# random.net
KiCad netlist of a schematic drawn in EAGLE
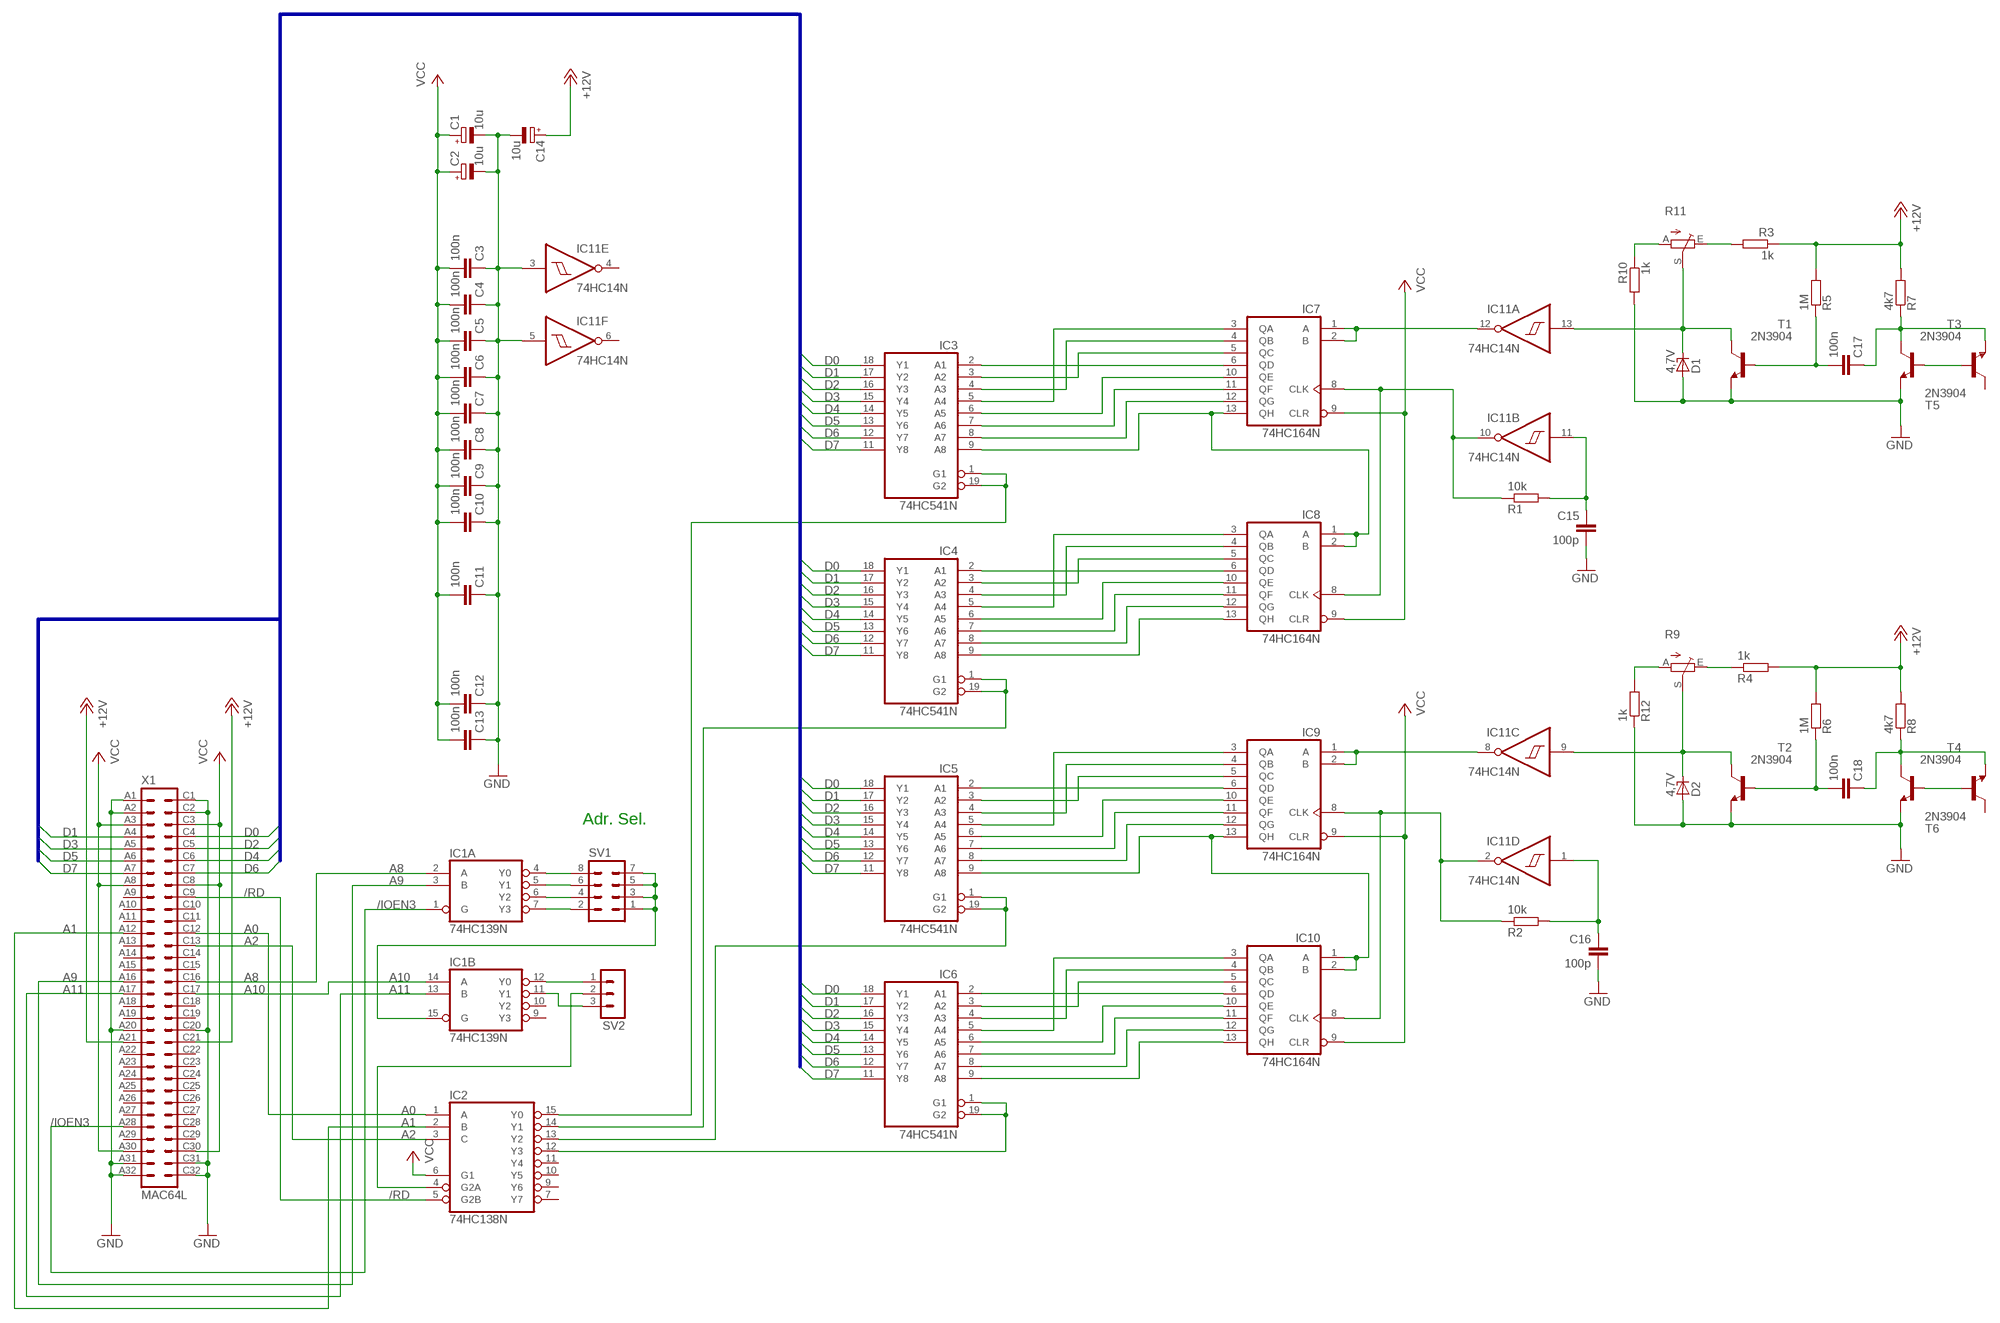
[diagram p0: schematic, sheet 1]

(export (version "E")
  (design (tool "Eeschema 10.0.6"))
  (components
    (comp (ref "C1")
      (value "10u")
      (footprint "eagle-import:TT2D4")
      (libsource (lib "eagle-import") (part "CPOL-EUTT2D4"))
    )
    (comp (ref "C2")
      (value "10u")
      (footprint "eagle-import:TT2D4")
      (libsource (lib "eagle-import") (part "CPOL-EUTT2D4"))
    )
    (comp (ref "C3")
      (value "100n")
      (footprint "eagle-import:C025-024X044")
      (libsource (lib "eagle-import") (part "C-EU025-024X044"))
    )
    (comp (ref "C4")
      (value "100n")
      (footprint "eagle-import:C025-024X044")
      (libsource (lib "eagle-import") (part "C-EU025-024X044"))
    )
    (comp (ref "C5")
      (value "100n")
      (footprint "eagle-import:C025-024X044")
      (libsource (lib "eagle-import") (part "C-EU025-024X044"))
    )
    (comp (ref "C6")
      (value "100n")
      (footprint "eagle-import:C025-024X044")
      (libsource (lib "eagle-import") (part "C-EU025-024X044"))
    )
    (comp (ref "C7")
      (value "100n")
      (footprint "eagle-import:C025-024X044")
      (libsource (lib "eagle-import") (part "C-EU025-024X044"))
    )
    (comp (ref "C8")
      (value "100n")
      (footprint "eagle-import:C025-024X044")
      (libsource (lib "eagle-import") (part "C-EU025-024X044"))
    )
    (comp (ref "C9")
      (value "100n")
      (footprint "eagle-import:C025-024X044")
      (libsource (lib "eagle-import") (part "C-EU025-024X044"))
    )
    (comp (ref "C10")
      (value "100n")
      (footprint "eagle-import:C025-024X044")
      (libsource (lib "eagle-import") (part "C-EU025-024X044"))
    )
    (comp (ref "C11")
      (value "100n")
      (footprint "eagle-import:C025-024X044")
      (libsource (lib "eagle-import") (part "C-EU025-024X044"))
    )
    (comp (ref "C12")
      (value "100n")
      (footprint "eagle-import:C025-024X044")
      (libsource (lib "eagle-import") (part "C-EU025-024X044"))
    )
    (comp (ref "C13")
      (value "100n")
      (footprint "eagle-import:C025-024X044")
      (libsource (lib "eagle-import") (part "C-EU025-024X044"))
    )
    (comp (ref "C14")
      (value "10u")
      (footprint "eagle-import:TT2D4")
      (libsource (lib "eagle-import") (part "CPOL-EUTT2D4"))
    )
    (comp (ref "C15")
      (value "100p")
      (footprint "eagle-import:C025-024X044")
      (libsource (lib "eagle-import") (part "C-EU025-024X044"))
    )
    (comp (ref "C16")
      (value "100p")
      (footprint "eagle-import:C025-024X044")
      (libsource (lib "eagle-import") (part "C-EU025-024X044"))
    )
    (comp (ref "C17")
      (value "100n")
      (footprint "eagle-import:C025-024X044")
      (libsource (lib "eagle-import") (part "C-EU025-024X044"))
    )
    (comp (ref "C18")
      (value "100n")
      (footprint "eagle-import:C025-024X044")
      (libsource (lib "eagle-import") (part "C-EU025-024X044"))
    )
    (comp (ref "D1")
      (value "4,7V")
      (footprint "eagle-import:ZDIO-7.5")
      (libsource (lib "eagle-import") (part "ZENER-DIODEZD-7.5"))
    )
    (comp (ref "D2")
      (value "4,7V")
      (footprint "eagle-import:ZDIO-7.5")
      (libsource (lib "eagle-import") (part "ZENER-DIODEZD-7.5"))
    )
    (comp (ref "IC1")
      (value "74HC139N")
      (footprint "eagle-import:DIL16")
      (libsource (lib "eagle-import") (part "74139NHC"))
    )
    (comp (ref "IC2")
      (value "74HC138N")
      (footprint "eagle-import:DIL16")
      (libsource (lib "eagle-import") (part "74138NHC"))
    )
    (comp (ref "IC3")
      (value "74HC541N")
      (footprint "eagle-import:DIL20")
      (libsource (lib "eagle-import") (part "74541NHC"))
    )
    (comp (ref "IC4")
      (value "74HC541N")
      (footprint "eagle-import:DIL20")
      (libsource (lib "eagle-import") (part "74541NHC"))
    )
    (comp (ref "IC5")
      (value "74HC541N")
      (footprint "eagle-import:DIL20")
      (libsource (lib "eagle-import") (part "74541NHC"))
    )
    (comp (ref "IC6")
      (value "74HC541N")
      (footprint "eagle-import:DIL20")
      (libsource (lib "eagle-import") (part "74541NHC"))
    )
    (comp (ref "IC7")
      (value "74HC164N")
      (footprint "eagle-import:DIL14")
      (libsource (lib "eagle-import") (part "74164NHC"))
    )
    (comp (ref "IC8")
      (value "74HC164N")
      (footprint "eagle-import:DIL14")
      (libsource (lib "eagle-import") (part "74164NHC"))
    )
    (comp (ref "IC9")
      (value "74HC164N")
      (footprint "eagle-import:DIL14")
      (libsource (lib "eagle-import") (part "74164NHC"))
    )
    (comp (ref "IC10")
      (value "74HC164N")
      (footprint "eagle-import:DIL14")
      (libsource (lib "eagle-import") (part "74164NHC"))
    )
    (comp (ref "IC11")
      (value "74HC14N")
      (footprint "eagle-import:DIL14")
      (libsource (lib "eagle-import") (part "7414NHC"))
    )
    (comp (ref "R1")
      (value "10k")
      (footprint "eagle-import:0204_7")
      (libsource (lib "eagle-import") (part "R-EU_0204/7"))
    )
    (comp (ref "R2")
      (value "10k")
      (footprint "eagle-import:0204_7")
      (libsource (lib "eagle-import") (part "R-EU_0204/7"))
    )
    (comp (ref "R3")
      (value "1k")
      (footprint "eagle-import:0204_7")
      (libsource (lib "eagle-import") (part "R-EU_0204/7"))
    )
    (comp (ref "R4")
      (value "1k")
      (footprint "eagle-import:0204_7")
      (libsource (lib "eagle-import") (part "R-EU_0204/7"))
    )
    (comp (ref "R5")
      (value "1M")
      (footprint "eagle-import:0204_7")
      (libsource (lib "eagle-import") (part "R-EU_0204/7"))
    )
    (comp (ref "R6")
      (value "1M")
      (footprint "eagle-import:0204_7")
      (libsource (lib "eagle-import") (part "R-EU_0204/7"))
    )
    (comp (ref "R7")
      (value "4k7")
      (footprint "eagle-import:0204_7")
      (libsource (lib "eagle-import") (part "R-EU_0204/7"))
    )
    (comp (ref "R8")
      (value "4k7")
      (footprint "eagle-import:0204_7")
      (libsource (lib "eagle-import") (part "R-EU_0204/7"))
    )
    (comp (ref "R9")
      (value "TRIM_EU-S63X")
      (footprint "eagle-import:S63X")
      (libsource (lib "eagle-import") (part "TRIM_EU-S63X"))
    )
    (comp (ref "R10")
      (value "1k")
      (footprint "eagle-import:0204_7")
      (libsource (lib "eagle-import") (part "R-EU_0204/7"))
    )
    (comp (ref "R11")
      (value "TRIM_EU-S63X")
      (footprint "eagle-import:S63X")
      (libsource (lib "eagle-import") (part "TRIM_EU-S63X"))
    )
    (comp (ref "R12")
      (value "1k")
      (footprint "eagle-import:0204_7")
      (libsource (lib "eagle-import") (part "R-EU_0204/7"))
    )
    (comp (ref "SV1")
      (value "MA04-2")
      (footprint "eagle-import:MA04-2")
      (libsource (lib "eagle-import") (part "MA04-2"))
    )
    (comp (ref "SV2")
      (value "MA03-1")
      (footprint "eagle-import:MA03-1")
      (libsource (lib "eagle-import") (part "MA03-1"))
    )
    (comp (ref "T1")
      (value "2N3904")
      (footprint "eagle-import:TO92")
      (libsource (lib "eagle-import") (part "2N3904"))
    )
    (comp (ref "T2")
      (value "2N3904")
      (footprint "eagle-import:TO92")
      (libsource (lib "eagle-import") (part "2N3904"))
    )
    (comp (ref "T3")
      (value "2N3904")
      (footprint "eagle-import:TO92")
      (libsource (lib "eagle-import") (part "2N3904"))
    )
    (comp (ref "T4")
      (value "2N3904")
      (footprint "eagle-import:TO92")
      (libsource (lib "eagle-import") (part "2N3904"))
    )
    (comp (ref "T5")
      (value "2N3904")
      (footprint "eagle-import:TO92")
      (libsource (lib "eagle-import") (part "2N3904"))
    )
    (comp (ref "T6")
      (value "2N3904")
      (footprint "eagle-import:TO92")
      (libsource (lib "eagle-import") (part "2N3904"))
    )
    (comp (ref "X1")
      (value "MAC64L")
      (footprint "eagle-import:MAC64L")
      (libsource (lib "eagle-import") (part "MAC64L"))
    )
  )
  (nets
    (net (code "1") (name "+12V") (class "Default")
      (node (ref "C14") (pin "+") (pinfunction "+_+") (pintype "passive"))
      (node (ref "R3") (pin "1") (pinfunction "1_1") (pintype "passive"))
      (node (ref "R4") (pin "2") (pinfunction "2_2") (pintype "passive"))
      (node (ref "R5") (pin "2") (pinfunction "2_2") (pintype "passive"))
      (node (ref "R6") (pin "2") (pinfunction "2_2") (pintype "passive"))
      (node (ref "R7") (pin "2") (pinfunction "2_2") (pintype "passive"))
      (node (ref "R8") (pin "2") (pinfunction "2_2") (pintype "passive"))
      (node (ref "X1") (pin "A21") (pinfunction "A21_A21") (pintype "passive"))
      (node (ref "X1") (pin "C21") (pinfunction "C21_C21") (pintype "passive"))
    )
    (net (code "2") (name "/A0") (class "Default")
      (node (ref "IC2") (pin "1") (pinfunction "A_1") (pintype "input"))
      (node (ref "X1") (pin "C12") (pinfunction "C12_C12") (pintype "passive"))
    )
    (net (code "3") (name "/A1") (class "Default")
      (node (ref "IC2") (pin "2") (pinfunction "B_2") (pintype "input"))
      (node (ref "X1") (pin "A12") (pinfunction "A12_A12") (pintype "passive"))
    )
    (net (code "4") (name "/A2") (class "Default")
      (node (ref "IC2") (pin "3") (pinfunction "C_3") (pintype "input"))
      (node (ref "X1") (pin "C13") (pinfunction "C13_C13") (pintype "passive"))
    )
    (net (code "5") (name "/A8") (class "Default")
      (node (ref "IC1") (pin "2") (pinfunction "A_2") (pintype "input"))
      (node (ref "X1") (pin "C16") (pinfunction "C16_C16") (pintype "passive"))
    )
    (net (code "6") (name "/A9") (class "Default")
      (node (ref "IC1") (pin "3") (pinfunction "B_3") (pintype "input"))
      (node (ref "X1") (pin "A16") (pinfunction "A16_A16") (pintype "passive"))
    )
    (net (code "7") (name "/A10") (class "Default")
      (node (ref "IC1") (pin "14") (pinfunction "A_14") (pintype "input"))
      (node (ref "X1") (pin "C17") (pinfunction "C17_C17") (pintype "passive"))
    )
    (net (code "8") (name "/A11") (class "Default")
      (node (ref "IC1") (pin "13") (pinfunction "B_13") (pintype "input"))
      (node (ref "X1") (pin "A17") (pinfunction "A17_A17") (pintype "passive"))
    )
    (net (code "9") (name "/D0") (class "Default")
      (node (ref "IC3") (pin "18") (pinfunction "Y1_18") (pintype "tri_state"))
      (node (ref "IC4") (pin "18") (pinfunction "Y1_18") (pintype "tri_state"))
      (node (ref "IC5") (pin "18") (pinfunction "Y1_18") (pintype "tri_state"))
      (node (ref "IC6") (pin "18") (pinfunction "Y1_18") (pintype "tri_state"))
      (node (ref "X1") (pin "C4") (pinfunction "C4_C4") (pintype "passive"))
    )
    (net (code "10") (name "/D1") (class "Default")
      (node (ref "IC3") (pin "17") (pinfunction "Y2_17") (pintype "tri_state"))
      (node (ref "IC4") (pin "17") (pinfunction "Y2_17") (pintype "tri_state"))
      (node (ref "IC5") (pin "17") (pinfunction "Y2_17") (pintype "tri_state"))
      (node (ref "IC6") (pin "17") (pinfunction "Y2_17") (pintype "tri_state"))
      (node (ref "X1") (pin "A4") (pinfunction "A4_A4") (pintype "passive"))
    )
    (net (code "11") (name "/D2") (class "Default")
      (node (ref "IC3") (pin "16") (pinfunction "Y3_16") (pintype "tri_state"))
      (node (ref "IC4") (pin "16") (pinfunction "Y3_16") (pintype "tri_state"))
      (node (ref "IC5") (pin "16") (pinfunction "Y3_16") (pintype "tri_state"))
      (node (ref "IC6") (pin "16") (pinfunction "Y3_16") (pintype "tri_state"))
      (node (ref "X1") (pin "C5") (pinfunction "C5_C5") (pintype "passive"))
    )
    (net (code "12") (name "/D3") (class "Default")
      (node (ref "IC3") (pin "15") (pinfunction "Y4_15") (pintype "tri_state"))
      (node (ref "IC4") (pin "15") (pinfunction "Y4_15") (pintype "tri_state"))
      (node (ref "IC5") (pin "15") (pinfunction "Y4_15") (pintype "tri_state"))
      (node (ref "IC6") (pin "15") (pinfunction "Y4_15") (pintype "tri_state"))
      (node (ref "X1") (pin "A5") (pinfunction "A5_A5") (pintype "passive"))
    )
    (net (code "13") (name "/D4") (class "Default")
      (node (ref "IC3") (pin "14") (pinfunction "Y5_14") (pintype "tri_state"))
      (node (ref "IC4") (pin "14") (pinfunction "Y5_14") (pintype "tri_state"))
      (node (ref "IC5") (pin "14") (pinfunction "Y5_14") (pintype "tri_state"))
      (node (ref "IC6") (pin "14") (pinfunction "Y5_14") (pintype "tri_state"))
      (node (ref "X1") (pin "C6") (pinfunction "C6_C6") (pintype "passive"))
    )
    (net (code "14") (name "/D5") (class "Default")
      (node (ref "IC3") (pin "13") (pinfunction "Y6_13") (pintype "tri_state"))
      (node (ref "IC4") (pin "13") (pinfunction "Y6_13") (pintype "tri_state"))
      (node (ref "IC5") (pin "13") (pinfunction "Y6_13") (pintype "tri_state"))
      (node (ref "IC6") (pin "13") (pinfunction "Y6_13") (pintype "tri_state"))
      (node (ref "X1") (pin "A6") (pinfunction "A6_A6") (pintype "passive"))
    )
    (net (code "15") (name "/D6") (class "Default")
      (node (ref "IC3") (pin "12") (pinfunction "Y7_12") (pintype "tri_state"))
      (node (ref "IC4") (pin "12") (pinfunction "Y7_12") (pintype "tri_state"))
      (node (ref "IC5") (pin "12") (pinfunction "Y7_12") (pintype "tri_state"))
      (node (ref "IC6") (pin "12") (pinfunction "Y7_12") (pintype "tri_state"))
      (node (ref "X1") (pin "C7") (pinfunction "C7_C7") (pintype "passive"))
    )
    (net (code "16") (name "/D7") (class "Default")
      (node (ref "IC3") (pin "11") (pinfunction "Y8_11") (pintype "tri_state"))
      (node (ref "IC4") (pin "11") (pinfunction "Y8_11") (pintype "tri_state"))
      (node (ref "IC5") (pin "11") (pinfunction "Y8_11") (pintype "tri_state"))
      (node (ref "IC6") (pin "11") (pinfunction "Y8_11") (pintype "tri_state"))
      (node (ref "X1") (pin "A7") (pinfunction "A7_A7") (pintype "passive"))
    )
    (net (code "17") (name "/{slash}IOEN3") (class "Default")
      (node (ref "IC1") (pin "1") (pinfunction "G_1") (pintype "input"))
      (node (ref "X1") (pin "A28") (pinfunction "A28_A28") (pintype "passive"))
    )
    (net (code "18") (name "/{slash}RD") (class "Default")
      (node (ref "IC2") (pin "5") (pinfunction "G2B_5") (pintype "input"))
      (node (ref "X1") (pin "C9") (pinfunction "C9_C9") (pintype "passive"))
    )
    (net (code "19") (name "GND") (class "Default")
      (node (ref "C1") (pin "-") (pinfunction "-_-") (pintype "passive"))
      (node (ref "C10") (pin "1") (pinfunction "1_1") (pintype "passive"))
      (node (ref "C11") (pin "1") (pinfunction "1_1") (pintype "passive"))
      (node (ref "C12") (pin "1") (pinfunction "1_1") (pintype "passive"))
      (node (ref "C13") (pin "1") (pinfunction "1_1") (pintype "passive"))
      (node (ref "C14") (pin "-") (pinfunction "-_-") (pintype "passive"))
      (node (ref "C15") (pin "2") (pinfunction "2_2") (pintype "passive"))
      (node (ref "C16") (pin "2") (pinfunction "2_2") (pintype "passive"))
      (node (ref "C2") (pin "-") (pinfunction "-_-") (pintype "passive"))
      (node (ref "C3") (pin "1") (pinfunction "1_1") (pintype "passive"))
      (node (ref "C4") (pin "1") (pinfunction "1_1") (pintype "passive"))
      (node (ref "C5") (pin "1") (pinfunction "1_1") (pintype "passive"))
      (node (ref "C6") (pin "1") (pinfunction "1_1") (pintype "passive"))
      (node (ref "C7") (pin "1") (pinfunction "1_1") (pintype "passive"))
      (node (ref "C8") (pin "1") (pinfunction "1_1") (pintype "passive"))
      (node (ref "C9") (pin "1") (pinfunction "1_1") (pintype "passive"))
      (node (ref "D1") (pin "A") (pinfunction "A_A") (pintype "passive"))
      (node (ref "D2") (pin "A") (pinfunction "A_A") (pintype "passive"))
      (node (ref "IC11") (pin "3") (pinfunction "I_3") (pintype "input"))
      (node (ref "IC11") (pin "5") (pinfunction "I_5") (pintype "input"))
      (node (ref "R10") (pin "2") (pinfunction "2_2") (pintype "passive"))
      (node (ref "R12") (pin "1") (pinfunction "1_1") (pintype "passive"))
      (node (ref "T1") (pin "3") (pinfunction "E_3") (pintype "passive"))
      (node (ref "T2") (pin "3") (pinfunction "E_3") (pintype "passive"))
      (node (ref "T3") (pin "3") (pinfunction "E_3") (pintype "passive"))
      (node (ref "T4") (pin "3") (pinfunction "E_3") (pintype "passive"))
      (node (ref "X1") (pin "A1") (pinfunction "A1_A1") (pintype "passive"))
      (node (ref "X1") (pin "A2") (pinfunction "A2_A2") (pintype "passive"))
      (node (ref "X1") (pin "A20") (pinfunction "A20_A20") (pintype "passive"))
      (node (ref "X1") (pin "A31") (pinfunction "A31_A31") (pintype "passive"))
      (node (ref "X1") (pin "A32") (pinfunction "A32_A32") (pintype "passive"))
      (node (ref "X1") (pin "C1") (pinfunction "C1_C1") (pintype "passive"))
      (node (ref "X1") (pin "C2") (pinfunction "C2_C2") (pintype "passive"))
      (node (ref "X1") (pin "C20") (pinfunction "C20_C20") (pintype "passive"))
      (node (ref "X1") (pin "C31") (pinfunction "C31_C31") (pintype "passive"))
      (node (ref "X1") (pin "C32") (pinfunction "C32_C32") (pintype "passive"))
    )
    (net (code "20") (name "Net-(IC1A-Y0)") (class "Default")
      (node (ref "IC1") (pin "4") (pinfunction "Y0_4") (pintype "output"))
      (node (ref "SV1") (pin "8") (pinfunction "8_8") (pintype "passive"))
    )
    (net (code "21") (name "Net-(IC1A-Y1)") (class "Default")
      (node (ref "IC1") (pin "5") (pinfunction "Y1_5") (pintype "output"))
      (node (ref "SV1") (pin "6") (pinfunction "6_6") (pintype "passive"))
    )
    (net (code "22") (name "Net-(IC1A-Y2)") (class "Default")
      (node (ref "IC1") (pin "6") (pinfunction "Y2_6") (pintype "output"))
      (node (ref "SV1") (pin "4") (pinfunction "4_4") (pintype "passive"))
    )
    (net (code "23") (name "Net-(IC1A-Y3)") (class "Default")
      (node (ref "IC1") (pin "7") (pinfunction "Y3_7") (pintype "output"))
      (node (ref "SV1") (pin "2") (pinfunction "2_2") (pintype "passive"))
    )
    (net (code "24") (name "Net-(IC1B-G)") (class "Default")
      (node (ref "IC1") (pin "15") (pinfunction "G_15") (pintype "input"))
      (node (ref "SV1") (pin "1") (pinfunction "1_1") (pintype "passive"))
      (node (ref "SV1") (pin "3") (pinfunction "3_3") (pintype "passive"))
      (node (ref "SV1") (pin "5") (pinfunction "5_5") (pintype "passive"))
      (node (ref "SV1") (pin "7") (pinfunction "7_7") (pintype "passive"))
    )
    (net (code "25") (name "Net-(IC1B-Y0)") (class "Default")
      (node (ref "IC1") (pin "12") (pinfunction "Y0_12") (pintype "output"))
      (node (ref "SV2") (pin "1") (pinfunction "1_1") (pintype "passive"))
    )
    (net (code "26") (name "Net-(IC1B-Y1)") (class "Default")
      (node (ref "IC1") (pin "11") (pinfunction "Y1_11") (pintype "output"))
      (node (ref "SV2") (pin "3") (pinfunction "3_3") (pintype "passive"))
    )
    (net (code "27") (name "Net-(IC2A-G2A)") (class "Default")
      (node (ref "IC2") (pin "4") (pinfunction "G2A_4") (pintype "input"))
      (node (ref "SV2") (pin "2") (pinfunction "2_2") (pintype "passive"))
    )
    (net (code "28") (name "Net-(IC2A-Y0)") (class "Default")
      (node (ref "IC2") (pin "15") (pinfunction "Y0_15") (pintype "output"))
      (node (ref "IC3") (pin "1") (pinfunction "G1_1") (pintype "input"))
      (node (ref "IC3") (pin "19") (pinfunction "G2_19") (pintype "input"))
    )
    (net (code "29") (name "Net-(IC2A-Y1)") (class "Default")
      (node (ref "IC2") (pin "14") (pinfunction "Y1_14") (pintype "output"))
      (node (ref "IC4") (pin "1") (pinfunction "G1_1") (pintype "input"))
      (node (ref "IC4") (pin "19") (pinfunction "G2_19") (pintype "input"))
    )
    (net (code "30") (name "Net-(IC2A-Y2)") (class "Default")
      (node (ref "IC2") (pin "13") (pinfunction "Y2_13") (pintype "output"))
      (node (ref "IC5") (pin "1") (pinfunction "G1_1") (pintype "input"))
      (node (ref "IC5") (pin "19") (pinfunction "G2_19") (pintype "input"))
    )
    (net (code "31") (name "Net-(IC2A-Y3)") (class "Default")
      (node (ref "IC2") (pin "12") (pinfunction "Y3_12") (pintype "output"))
      (node (ref "IC6") (pin "1") (pinfunction "G1_1") (pintype "input"))
      (node (ref "IC6") (pin "19") (pinfunction "G2_19") (pintype "input"))
    )
    (net (code "32") (name "Net-(IC3A-A1)") (class "Default")
      (node (ref "IC3") (pin "2") (pinfunction "A1_2") (pintype "input"))
      (node (ref "IC7") (pin "6") (pinfunction "QD_6") (pintype "output"))
    )
    (net (code "33") (name "Net-(IC3A-A2)") (class "Default")
      (node (ref "IC3") (pin "3") (pinfunction "A2_3") (pintype "input"))
      (node (ref "IC7") (pin "5") (pinfunction "QC_5") (pintype "output"))
    )
    (net (code "34") (name "Net-(IC3A-A3)") (class "Default")
      (node (ref "IC3") (pin "4") (pinfunction "A3_4") (pintype "input"))
      (node (ref "IC7") (pin "4") (pinfunction "QB_4") (pintype "output"))
    )
    (net (code "35") (name "Net-(IC3A-A4)") (class "Default")
      (node (ref "IC3") (pin "5") (pinfunction "A4_5") (pintype "input"))
      (node (ref "IC7") (pin "3") (pinfunction "QA_3") (pintype "output"))
    )
    (net (code "36") (name "Net-(IC3A-A5)") (class "Default")
      (node (ref "IC3") (pin "6") (pinfunction "A5_6") (pintype "input"))
      (node (ref "IC7") (pin "10") (pinfunction "QE_10") (pintype "output"))
    )
    (net (code "37") (name "Net-(IC3A-A6)") (class "Default")
      (node (ref "IC3") (pin "7") (pinfunction "A6_7") (pintype "input"))
      (node (ref "IC7") (pin "11") (pinfunction "QF_11") (pintype "output"))
    )
    (net (code "38") (name "Net-(IC3A-A7)") (class "Default")
      (node (ref "IC3") (pin "8") (pinfunction "A7_8") (pintype "input"))
      (node (ref "IC7") (pin "12") (pinfunction "QG_12") (pintype "output"))
    )
    (net (code "39") (name "Net-(IC3A-A8)") (class "Default")
      (node (ref "IC3") (pin "9") (pinfunction "A8_9") (pintype "input"))
      (node (ref "IC7") (pin "13") (pinfunction "QH_13") (pintype "output"))
      (node (ref "IC8") (pin "1") (pinfunction "A_1") (pintype "input"))
      (node (ref "IC8") (pin "2") (pinfunction "B_2") (pintype "input"))
    )
    (net (code "40") (name "Net-(IC4A-A1)") (class "Default")
      (node (ref "IC4") (pin "2") (pinfunction "A1_2") (pintype "input"))
      (node (ref "IC8") (pin "6") (pinfunction "QD_6") (pintype "output"))
    )
    (net (code "41") (name "Net-(IC4A-A2)") (class "Default")
      (node (ref "IC4") (pin "3") (pinfunction "A2_3") (pintype "input"))
      (node (ref "IC8") (pin "5") (pinfunction "QC_5") (pintype "output"))
    )
    (net (code "42") (name "Net-(IC4A-A3)") (class "Default")
      (node (ref "IC4") (pin "4") (pinfunction "A3_4") (pintype "input"))
      (node (ref "IC8") (pin "4") (pinfunction "QB_4") (pintype "output"))
    )
    (net (code "43") (name "Net-(IC4A-A4)") (class "Default")
      (node (ref "IC4") (pin "5") (pinfunction "A4_5") (pintype "input"))
      (node (ref "IC8") (pin "3") (pinfunction "QA_3") (pintype "output"))
    )
    (net (code "44") (name "Net-(IC4A-A5)") (class "Default")
      (node (ref "IC4") (pin "6") (pinfunction "A5_6") (pintype "input"))
      (node (ref "IC8") (pin "10") (pinfunction "QE_10") (pintype "output"))
    )
    (net (code "45") (name "Net-(IC4A-A6)") (class "Default")
      (node (ref "IC4") (pin "7") (pinfunction "A6_7") (pintype "input"))
      (node (ref "IC8") (pin "11") (pinfunction "QF_11") (pintype "output"))
    )
    (net (code "46") (name "Net-(IC4A-A7)") (class "Default")
      (node (ref "IC4") (pin "8") (pinfunction "A7_8") (pintype "input"))
      (node (ref "IC8") (pin "12") (pinfunction "QG_12") (pintype "output"))
    )
    (net (code "47") (name "Net-(IC4A-A8)") (class "Default")
      (node (ref "IC4") (pin "9") (pinfunction "A8_9") (pintype "input"))
      (node (ref "IC8") (pin "13") (pinfunction "QH_13") (pintype "output"))
    )
    (net (code "48") (name "Net-(IC5A-A1)") (class "Default")
      (node (ref "IC5") (pin "2") (pinfunction "A1_2") (pintype "input"))
      (node (ref "IC9") (pin "6") (pinfunction "QD_6") (pintype "output"))
    )
    (net (code "49") (name "Net-(IC5A-A2)") (class "Default")
      (node (ref "IC5") (pin "3") (pinfunction "A2_3") (pintype "input"))
      (node (ref "IC9") (pin "5") (pinfunction "QC_5") (pintype "output"))
    )
    (net (code "50") (name "Net-(IC5A-A3)") (class "Default")
      (node (ref "IC5") (pin "4") (pinfunction "A3_4") (pintype "input"))
      (node (ref "IC9") (pin "4") (pinfunction "QB_4") (pintype "output"))
    )
    (net (code "51") (name "Net-(IC5A-A4)") (class "Default")
      (node (ref "IC5") (pin "5") (pinfunction "A4_5") (pintype "input"))
      (node (ref "IC9") (pin "3") (pinfunction "QA_3") (pintype "output"))
    )
    (net (code "52") (name "Net-(IC5A-A5)") (class "Default")
      (node (ref "IC5") (pin "6") (pinfunction "A5_6") (pintype "input"))
      (node (ref "IC9") (pin "10") (pinfunction "QE_10") (pintype "output"))
    )
    (net (code "53") (name "Net-(IC5A-A6)") (class "Default")
      (node (ref "IC5") (pin "7") (pinfunction "A6_7") (pintype "input"))
      (node (ref "IC9") (pin "11") (pinfunction "QF_11") (pintype "output"))
    )
    (net (code "54") (name "Net-(IC5A-A7)") (class "Default")
      (node (ref "IC5") (pin "8") (pinfunction "A7_8") (pintype "input"))
      (node (ref "IC9") (pin "12") (pinfunction "QG_12") (pintype "output"))
    )
    (net (code "55") (name "Net-(IC10A-A)") (class "Default")
      (node (ref "IC10") (pin "1") (pinfunction "A_1") (pintype "input"))
      (node (ref "IC10") (pin "2") (pinfunction "B_2") (pintype "input"))
      (node (ref "IC5") (pin "9") (pinfunction "A8_9") (pintype "input"))
      (node (ref "IC9") (pin "13") (pinfunction "QH_13") (pintype "output"))
    )
    (net (code "56") (name "Net-(IC10A-CLK)") (class "Default")
      (node (ref "IC10") (pin "8") (pinfunction "CLK_8") (pintype "input"))
      (node (ref "IC11") (pin "2") (pinfunction "O_2") (pintype "output"))
      (node (ref "IC9") (pin "8") (pinfunction "CLK_8") (pintype "input"))
      (node (ref "R2") (pin "1") (pinfunction "1_1") (pintype "passive"))
    )
    (net (code "57") (name "Net-(IC10A-QA)") (class "Default")
      (node (ref "IC10") (pin "3") (pinfunction "QA_3") (pintype "output"))
      (node (ref "IC6") (pin "5") (pinfunction "A4_5") (pintype "input"))
    )
    (net (code "58") (name "Net-(IC10A-QB)") (class "Default")
      (node (ref "IC10") (pin "4") (pinfunction "QB_4") (pintype "output"))
      (node (ref "IC6") (pin "4") (pinfunction "A3_4") (pintype "input"))
    )
    (net (code "59") (name "Net-(IC10A-QC)") (class "Default")
      (node (ref "IC10") (pin "5") (pinfunction "QC_5") (pintype "output"))
      (node (ref "IC6") (pin "3") (pinfunction "A2_3") (pintype "input"))
    )
    (net (code "60") (name "Net-(IC10A-QD)") (class "Default")
      (node (ref "IC10") (pin "6") (pinfunction "QD_6") (pintype "output"))
      (node (ref "IC6") (pin "2") (pinfunction "A1_2") (pintype "input"))
    )
    (net (code "61") (name "Net-(IC10A-QE)") (class "Default")
      (node (ref "IC10") (pin "10") (pinfunction "QE_10") (pintype "output"))
      (node (ref "IC6") (pin "6") (pinfunction "A5_6") (pintype "input"))
    )
    (net (code "62") (name "Net-(IC10A-QF)") (class "Default")
      (node (ref "IC10") (pin "11") (pinfunction "QF_11") (pintype "output"))
      (node (ref "IC6") (pin "7") (pinfunction "A6_7") (pintype "input"))
    )
    (net (code "63") (name "Net-(IC10A-QG)") (class "Default")
      (node (ref "IC10") (pin "12") (pinfunction "QG_12") (pintype "output"))
      (node (ref "IC6") (pin "8") (pinfunction "A7_8") (pintype "input"))
    )
    (net (code "64") (name "Net-(IC10A-QH)") (class "Default")
      (node (ref "IC10") (pin "13") (pinfunction "QH_13") (pintype "output"))
      (node (ref "IC6") (pin "9") (pinfunction "A8_9") (pintype "input"))
    )
    (net (code "65") (name "Net-(IC11A-I)") (class "Default")
      (node (ref "D1") (pin "C") (pinfunction "C_C") (pintype "passive"))
      (node (ref "IC11") (pin "13") (pinfunction "I_13") (pintype "input"))
      (node (ref "R11") (pin "S") (pinfunction "S_S") (pintype "passive"))
      (node (ref "T1") (pin "1") (pinfunction "C_1") (pintype "passive"))
    )
    (net (code "66") (name "Net-(IC11A-O)") (class "Default")
      (node (ref "IC11") (pin "12") (pinfunction "O_12") (pintype "output"))
      (node (ref "IC7") (pin "1") (pinfunction "A_1") (pintype "input"))
      (node (ref "IC7") (pin "2") (pinfunction "B_2") (pintype "input"))
    )
    (net (code "67") (name "Net-(IC11B-I)") (class "Default")
      (node (ref "C15") (pin "1") (pinfunction "1_1") (pintype "passive"))
      (node (ref "IC11") (pin "11") (pinfunction "I_11") (pintype "input"))
      (node (ref "R1") (pin "2") (pinfunction "2_2") (pintype "passive"))
    )
    (net (code "68") (name "Net-(IC11B-O)") (class "Default")
      (node (ref "IC11") (pin "10") (pinfunction "O_10") (pintype "output"))
      (node (ref "IC7") (pin "8") (pinfunction "CLK_8") (pintype "input"))
      (node (ref "IC8") (pin "8") (pinfunction "CLK_8") (pintype "input"))
      (node (ref "R1") (pin "1") (pinfunction "1_1") (pintype "passive"))
    )
    (net (code "69") (name "Net-(IC11C-I)") (class "Default")
      (node (ref "D2") (pin "C") (pinfunction "C_C") (pintype "passive"))
      (node (ref "IC11") (pin "9") (pinfunction "I_9") (pintype "input"))
      (node (ref "R9") (pin "S") (pinfunction "S_S") (pintype "passive"))
      (node (ref "T2") (pin "1") (pinfunction "C_1") (pintype "passive"))
    )
    (net (code "70") (name "Net-(IC11C-O)") (class "Default")
      (node (ref "IC11") (pin "8") (pinfunction "O_8") (pintype "output"))
      (node (ref "IC9") (pin "1") (pinfunction "A_1") (pintype "input"))
      (node (ref "IC9") (pin "2") (pinfunction "B_2") (pintype "input"))
    )
    (net (code "71") (name "Net-(IC11D-I)") (class "Default")
      (node (ref "C16") (pin "1") (pinfunction "1_1") (pintype "passive"))
      (node (ref "IC11") (pin "1") (pinfunction "I_1") (pintype "input"))
      (node (ref "R2") (pin "2") (pinfunction "2_2") (pintype "passive"))
    )
    (net (code "72") (name "Net-(R4-Pad1)") (class "Default")
      (node (ref "R4") (pin "1") (pinfunction "1_1") (pintype "passive"))
      (node (ref "R9") (pin "E") (pinfunction "E_E") (pintype "passive"))
    )
    (net (code "73") (name "Net-(R10-Pad1)") (class "Default")
      (node (ref "R10") (pin "1") (pinfunction "1_1") (pintype "passive"))
      (node (ref "R11") (pin "A") (pinfunction "A_A") (pintype "passive"))
    )
    (net (code "74") (name "Net-(R11-PadE)") (class "Default")
      (node (ref "R11") (pin "E") (pinfunction "E_E") (pintype "passive"))
      (node (ref "R3") (pin "2") (pinfunction "2_2") (pintype "passive"))
    )
    (net (code "75") (name "Net-(R12-Pad2)") (class "Default")
      (node (ref "R12") (pin "2") (pinfunction "2_2") (pintype "passive"))
      (node (ref "R9") (pin "A") (pinfunction "A_A") (pintype "passive"))
    )
    (net (code "76") (name "Net-(T1-B)") (class "Default")
      (node (ref "C17") (pin "2") (pinfunction "2_2") (pintype "passive"))
      (node (ref "R5") (pin "1") (pinfunction "1_1") (pintype "passive"))
      (node (ref "T1") (pin "2") (pinfunction "B_2") (pintype "passive"))
    )
    (net (code "77") (name "Net-(T2-B)") (class "Default")
      (node (ref "C18") (pin "2") (pinfunction "2_2") (pintype "passive"))
      (node (ref "R6") (pin "1") (pinfunction "1_1") (pintype "passive"))
      (node (ref "T2") (pin "2") (pinfunction "B_2") (pintype "passive"))
    )
    (net (code "78") (name "Net-(T3-B)") (class "Default")
      (node (ref "T3") (pin "2") (pinfunction "B_2") (pintype "passive"))
      (node (ref "T5") (pin "2") (pinfunction "B_2") (pintype "passive"))
    )
    (net (code "79") (name "Net-(T3-C)") (class "Default")
      (node (ref "C17") (pin "1") (pinfunction "1_1") (pintype "passive"))
      (node (ref "R7") (pin "1") (pinfunction "1_1") (pintype "passive"))
      (node (ref "T3") (pin "1") (pinfunction "C_1") (pintype "passive"))
      (node (ref "T5") (pin "3") (pinfunction "E_3") (pintype "passive"))
    )
    (net (code "80") (name "Net-(T4-B)") (class "Default")
      (node (ref "T4") (pin "2") (pinfunction "B_2") (pintype "passive"))
      (node (ref "T6") (pin "2") (pinfunction "B_2") (pintype "passive"))
    )
    (net (code "81") (name "Net-(T4-C)") (class "Default")
      (node (ref "C18") (pin "1") (pinfunction "1_1") (pintype "passive"))
      (node (ref "R8") (pin "1") (pinfunction "1_1") (pintype "passive"))
      (node (ref "T4") (pin "1") (pinfunction "C_1") (pintype "passive"))
      (node (ref "T6") (pin "3") (pinfunction "E_3") (pintype "passive"))
    )
    (net (code "82") (name "VCC") (class "Default")
      (node (ref "C1") (pin "+") (pinfunction "+_+") (pintype "passive"))
      (node (ref "C10") (pin "2") (pinfunction "2_2") (pintype "passive"))
      (node (ref "C11") (pin "2") (pinfunction "2_2") (pintype "passive"))
      (node (ref "C12") (pin "2") (pinfunction "2_2") (pintype "passive"))
      (node (ref "C13") (pin "2") (pinfunction "2_2") (pintype "passive"))
      (node (ref "C2") (pin "+") (pinfunction "+_+") (pintype "passive"))
      (node (ref "C3") (pin "2") (pinfunction "2_2") (pintype "passive"))
      (node (ref "C4") (pin "2") (pinfunction "2_2") (pintype "passive"))
      (node (ref "C5") (pin "2") (pinfunction "2_2") (pintype "passive"))
      (node (ref "C6") (pin "2") (pinfunction "2_2") (pintype "passive"))
      (node (ref "C7") (pin "2") (pinfunction "2_2") (pintype "passive"))
      (node (ref "C8") (pin "2") (pinfunction "2_2") (pintype "passive"))
      (node (ref "C9") (pin "2") (pinfunction "2_2") (pintype "passive"))
      (node (ref "IC10") (pin "9") (pinfunction "CLR_9") (pintype "input"))
      (node (ref "IC2") (pin "6") (pinfunction "G1_6") (pintype "input"))
      (node (ref "IC7") (pin "9") (pinfunction "CLR_9") (pintype "input"))
      (node (ref "IC8") (pin "9") (pinfunction "CLR_9") (pintype "input"))
      (node (ref "IC9") (pin "9") (pinfunction "CLR_9") (pintype "input"))
      (node (ref "X1") (pin "A3") (pinfunction "A3_A3") (pintype "passive"))
      (node (ref "X1") (pin "A30") (pinfunction "A30_A30") (pintype "passive"))
      (node (ref "X1") (pin "A8") (pinfunction "A8_A8") (pintype "passive"))
      (node (ref "X1") (pin "C3") (pinfunction "C3_C3") (pintype "passive"))
      (node (ref "X1") (pin "C30") (pinfunction "C30_C30") (pintype "passive"))
      (node (ref "X1") (pin "C8") (pinfunction "C8_C8") (pintype "passive"))
    )
    (net (code "83") (name "unconnected-(IC1B-Y2-Pad10)") (class "Default")
      (node (ref "IC1") (pin "10") (pinfunction "Y2_10") (pintype "output"))
    )
    (net (code "84") (name "unconnected-(IC1B-Y3-Pad9)") (class "Default")
      (node (ref "IC1") (pin "9") (pinfunction "Y3_9") (pintype "output"))
    )
    (net (code "85") (name "unconnected-(IC2A-Y4-Pad11)") (class "Default")
      (node (ref "IC2") (pin "11") (pinfunction "Y4_11") (pintype "output"))
    )
    (net (code "86") (name "unconnected-(IC2A-Y5-Pad10)") (class "Default")
      (node (ref "IC2") (pin "10") (pinfunction "Y5_10") (pintype "output"))
    )
    (net (code "87") (name "unconnected-(IC2A-Y6-Pad9)") (class "Default")
      (node (ref "IC2") (pin "9") (pinfunction "Y6_9") (pintype "output"))
    )
    (net (code "88") (name "unconnected-(IC2A-Y7-Pad7)") (class "Default")
      (node (ref "IC2") (pin "7") (pinfunction "Y7_7") (pintype "output"))
    )
    (net (code "89") (name "unconnected-(IC11E-O-Pad4)") (class "Default")
      (node (ref "IC11") (pin "4") (pinfunction "O_4") (pintype "output"))
    )
    (net (code "90") (name "unconnected-(IC11F-O-Pad6)") (class "Default")
      (node (ref "IC11") (pin "6") (pinfunction "O_6") (pintype "output"))
    )
    (net (code "91") (name "unconnected-(T5-C-Pad1)") (class "Default")
      (node (ref "T5") (pin "1") (pinfunction "C_1") (pintype "passive"))
    )
    (net (code "92") (name "unconnected-(T6-C-Pad1)") (class "Default")
      (node (ref "T6") (pin "1") (pinfunction "C_1") (pintype "passive"))
    )
    (net (code "93") (name "unconnected-(X1-PadA9)") (class "Default")
      (node (ref "X1") (pin "A9") (pinfunction "A9_A9") (pintype "passive"))
    )
    (net (code "94") (name "unconnected-(X1-PadA10)") (class "Default")
      (node (ref "X1") (pin "A10") (pinfunction "A10_A10") (pintype "passive"))
    )
    (net (code "95") (name "unconnected-(X1-PadA11)") (class "Default")
      (node (ref "X1") (pin "A11") (pinfunction "A11_A11") (pintype "passive"))
    )
    (net (code "96") (name "unconnected-(X1-PadA13)") (class "Default")
      (node (ref "X1") (pin "A13") (pinfunction "A13_A13") (pintype "passive"))
    )
    (net (code "97") (name "unconnected-(X1-PadA14)") (class "Default")
      (node (ref "X1") (pin "A14") (pinfunction "A14_A14") (pintype "passive"))
    )
    (net (code "98") (name "unconnected-(X1-PadA15)") (class "Default")
      (node (ref "X1") (pin "A15") (pinfunction "A15_A15") (pintype "passive"))
    )
    (net (code "99") (name "unconnected-(X1-PadA18)") (class "Default")
      (node (ref "X1") (pin "A18") (pinfunction "A18_A18") (pintype "passive"))
    )
    (net (code "100") (name "unconnected-(X1-PadA19)") (class "Default")
      (node (ref "X1") (pin "A19") (pinfunction "A19_A19") (pintype "passive"))
    )
    (net (code "101") (name "unconnected-(X1-PadA22)") (class "Default")
      (node (ref "X1") (pin "A22") (pinfunction "A22_A22") (pintype "passive"))
    )
    (net (code "102") (name "unconnected-(X1-PadA23)") (class "Default")
      (node (ref "X1") (pin "A23") (pinfunction "A23_A23") (pintype "passive"))
    )
    (net (code "103") (name "unconnected-(X1-PadA24)") (class "Default")
      (node (ref "X1") (pin "A24") (pinfunction "A24_A24") (pintype "passive"))
    )
    (net (code "104") (name "unconnected-(X1-PadA25)") (class "Default")
      (node (ref "X1") (pin "A25") (pinfunction "A25_A25") (pintype "passive"))
    )
    (net (code "105") (name "unconnected-(X1-PadA26)") (class "Default")
      (node (ref "X1") (pin "A26") (pinfunction "A26_A26") (pintype "passive"))
    )
    (net (code "106") (name "unconnected-(X1-PadA27)") (class "Default")
      (node (ref "X1") (pin "A27") (pinfunction "A27_A27") (pintype "passive"))
    )
    (net (code "107") (name "unconnected-(X1-PadA29)") (class "Default")
      (node (ref "X1") (pin "A29") (pinfunction "A29_A29") (pintype "passive"))
    )
    (net (code "108") (name "unconnected-(X1-PadC10)") (class "Default")
      (node (ref "X1") (pin "C10") (pinfunction "C10_C10") (pintype "passive"))
    )
    (net (code "109") (name "unconnected-(X1-PadC11)") (class "Default")
      (node (ref "X1") (pin "C11") (pinfunction "C11_C11") (pintype "passive"))
    )
    (net (code "110") (name "unconnected-(X1-PadC14)") (class "Default")
      (node (ref "X1") (pin "C14") (pinfunction "C14_C14") (pintype "passive"))
    )
    (net (code "111") (name "unconnected-(X1-PadC15)") (class "Default")
      (node (ref "X1") (pin "C15") (pinfunction "C15_C15") (pintype "passive"))
    )
    (net (code "112") (name "unconnected-(X1-PadC18)") (class "Default")
      (node (ref "X1") (pin "C18") (pinfunction "C18_C18") (pintype "passive"))
    )
    (net (code "113") (name "unconnected-(X1-PadC19)") (class "Default")
      (node (ref "X1") (pin "C19") (pinfunction "C19_C19") (pintype "passive"))
    )
    (net (code "114") (name "unconnected-(X1-PadC22)") (class "Default")
      (node (ref "X1") (pin "C22") (pinfunction "C22_C22") (pintype "passive"))
    )
    (net (code "115") (name "unconnected-(X1-PadC23)") (class "Default")
      (node (ref "X1") (pin "C23") (pinfunction "C23_C23") (pintype "passive"))
    )
    (net (code "116") (name "unconnected-(X1-PadC24)") (class "Default")
      (node (ref "X1") (pin "C24") (pinfunction "C24_C24") (pintype "passive"))
    )
    (net (code "117") (name "unconnected-(X1-PadC25)") (class "Default")
      (node (ref "X1") (pin "C25") (pinfunction "C25_C25") (pintype "passive"))
    )
    (net (code "118") (name "unconnected-(X1-PadC26)") (class "Default")
      (node (ref "X1") (pin "C26") (pinfunction "C26_C26") (pintype "passive"))
    )
    (net (code "119") (name "unconnected-(X1-PadC27)") (class "Default")
      (node (ref "X1") (pin "C27") (pinfunction "C27_C27") (pintype "passive"))
    )
    (net (code "120") (name "unconnected-(X1-PadC28)") (class "Default")
      (node (ref "X1") (pin "C28") (pinfunction "C28_C28") (pintype "passive"))
    )
    (net (code "121") (name "unconnected-(X1-PadC29)") (class "Default")
      (node (ref "X1") (pin "C29") (pinfunction "C29_C29") (pintype "passive"))
    )
  )
)
